# AC-DC_5V_Power_Supply.net
KiCad netlist of a schematic drawn in EAGLE
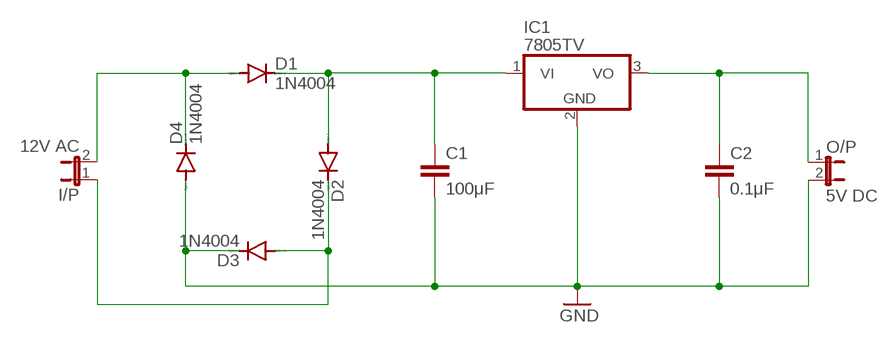
[diagram p0: schematic, sheet 1]

(export (version "E")
  (design (tool "Eeschema 10.0.6"))
  (components
    (comp (ref "C1")
      (value "100μF")
      (footprint "eagle-import:C2.5-2")
      (libsource (lib "eagle-import") (part "C2.5/2"))
    )
    (comp (ref "C2")
      (value "0.1μF")
      (footprint "eagle-import:C2.5-2")
      (libsource (lib "eagle-import") (part "C2.5/2"))
    )
    (comp (ref "D1")
      (value "1N4004")
      (footprint "eagle-import:DO41-10")
      (libsource (lib "eagle-import") (part "1N4004"))
    )
    (comp (ref "D2")
      (value "1N4004")
      (footprint "eagle-import:DO41-10")
      (libsource (lib "eagle-import") (part "1N4004"))
    )
    (comp (ref "D3")
      (value "1N4004")
      (footprint "eagle-import:DO41-10")
      (libsource (lib "eagle-import") (part "1N4004"))
    )
    (comp (ref "D4")
      (value "1N4004")
      (footprint "eagle-import:DO41-10")
      (libsource (lib "eagle-import") (part "1N4004"))
    )
    (comp (ref "I/P")
      (value "12V AC")
      (footprint "eagle-import:JP1")
      (libsource (lib "eagle-import") (part "JP1E"))
    )
    (comp (ref "IC1")
      (value "7805TV")
      (footprint "eagle-import:TO220V")
      (libsource (lib "eagle-import") (part "78TV05"))
    )
    (comp (ref "O/P")
      (value "5V DC")
      (footprint "eagle-import:JP1")
      (libsource (lib "eagle-import") (part "JP1E"))
    )
  )
  (nets
    (net (code "1") (name "GND") (class "Default")
      (node (ref "C1") (pin "2") (pinfunction "2_2") (pintype "passive"))
      (node (ref "C2") (pin "2") (pinfunction "2_2") (pintype "passive"))
      (node (ref "D3") (pin "C") (pinfunction "C_C") (pintype "passive"))
      (node (ref "D4") (pin "A") (pinfunction "A_A") (pintype "passive"))
      (node (ref "IC1") (pin "2") (pinfunction "GND_2") (pintype "passive"))
      (node (ref "O/P") (pin "2") (pinfunction "2_2") (pintype "passive"))
    )
    (net (code "2") (name "Net-(D1-PadA)") (class "Default")
      (node (ref "D1") (pin "A") (pinfunction "A_A") (pintype "passive"))
      (node (ref "D4") (pin "C") (pinfunction "C_C") (pintype "passive"))
      (node (ref "I/P") (pin "2") (pinfunction "2_2") (pintype "passive"))
    )
    (net (code "3") (name "Net-(D2-PadC)") (class "Default")
      (node (ref "D2") (pin "C") (pinfunction "C_C") (pintype "passive"))
      (node (ref "D3") (pin "A") (pinfunction "A_A") (pintype "passive"))
      (node (ref "I/P") (pin "1") (pinfunction "1_1") (pintype "passive"))
    )
    (net (code "4") (name "Net-(IC1-VI)") (class "Default")
      (node (ref "C1") (pin "1") (pinfunction "1_1") (pintype "passive"))
      (node (ref "D1") (pin "C") (pinfunction "C_C") (pintype "passive"))
      (node (ref "D2") (pin "A") (pinfunction "A_A") (pintype "passive"))
      (node (ref "IC1") (pin "1") (pinfunction "VI_1") (pintype "input"))
    )
    (net (code "5") (name "Net-(IC1-VO)") (class "Default")
      (node (ref "C2") (pin "1") (pinfunction "1_1") (pintype "passive"))
      (node (ref "IC1") (pin "3") (pinfunction "VO_3") (pintype "passive"))
      (node (ref "O/P") (pin "1") (pinfunction "1_1") (pintype "passive"))
    )
  )
)
